# WirelessTransceiver_RevB.net
KiCad netlist of a schematic drawn in EAGLE
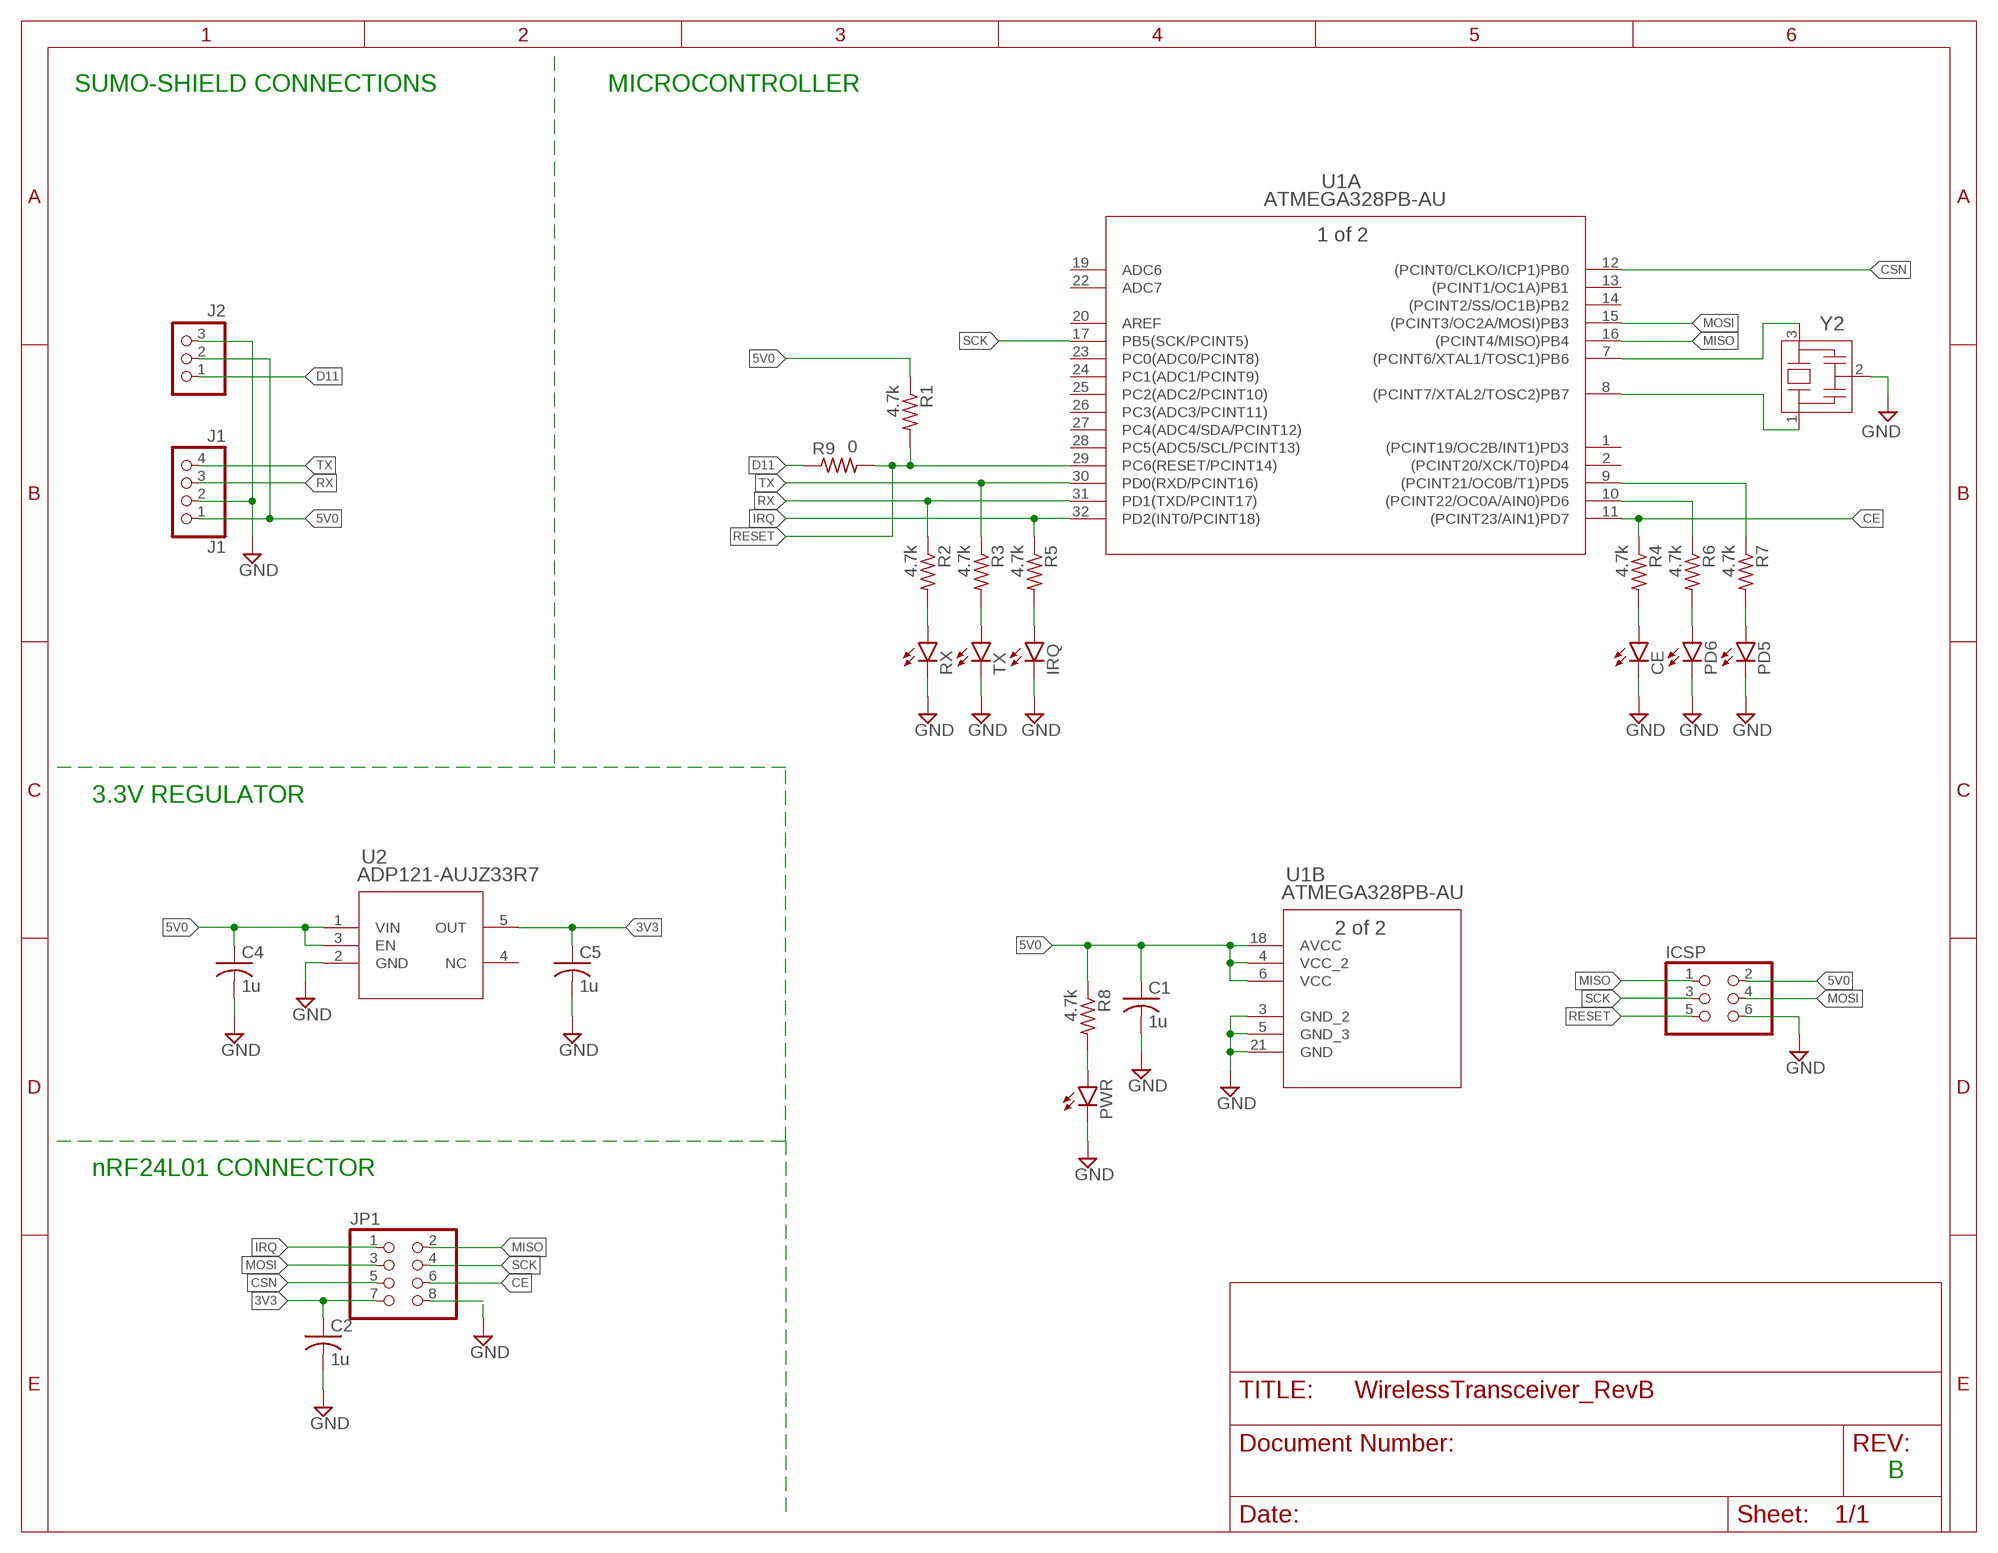
[diagram p0: schematic, sheet 1]

(export (version "E")
  (design (tool "Eeschema 10.0.6"))
  (components
    (comp (ref "C1")
      (value "1u")
      (footprint "eagle-import:C0805")
      (libsource (lib "eagle-import") (part "C-USC0805"))
    )
    (comp (ref "C2")
      (value "1u")
      (footprint "eagle-import:C0805")
      (libsource (lib "eagle-import") (part "C-USC0805"))
    )
    (comp (ref "C4")
      (value "1u")
      (footprint "eagle-import:C0805")
      (libsource (lib "eagle-import") (part "C-USC0805"))
    )
    (comp (ref "C5")
      (value "1u")
      (footprint "eagle-import:C0805")
      (libsource (lib "eagle-import") (part "C-USC0805"))
    )
    (comp (ref "CE")
      (value "LEDSML0805")
      (footprint "eagle-import:SML0805")
      (libsource (lib "eagle-import") (part "LEDSML0805"))
    )
    (comp (ref "ICSP")
      (value "PINHD-2X3")
      (footprint "eagle-import:2X03")
      (libsource (lib "eagle-import") (part "PINHD-2X3"))
    )
    (comp (ref "IRQ")
      (value "LEDSML0805")
      (footprint "eagle-import:SML0805")
      (libsource (lib "eagle-import") (part "LEDSML0805"))
    )
    (comp (ref "J1")
      (value "J1")
      (footprint "eagle-import:1X04")
      (libsource (lib "eagle-import") (part "PINHD-1X4"))
    )
    (comp (ref "J2")
      (value "PINHD-1X3")
      (footprint "eagle-import:1X03")
      (libsource (lib "eagle-import") (part "PINHD-1X3"))
    )
    (comp (ref "JP1")
      (value "PINHD-2X4")
      (footprint "eagle-import:2X04")
      (libsource (lib "eagle-import") (part "PINHD-2X4"))
    )
    (comp (ref "PD5")
      (value "LEDSML0805")
      (footprint "eagle-import:SML0805")
      (libsource (lib "eagle-import") (part "LEDSML0805"))
    )
    (comp (ref "PD6")
      (value "LEDSML0805")
      (footprint "eagle-import:SML0805")
      (libsource (lib "eagle-import") (part "LEDSML0805"))
    )
    (comp (ref "PWR")
      (value "LEDSML0805")
      (footprint "eagle-import:SML0805")
      (libsource (lib "eagle-import") (part "LEDSML0805"))
    )
    (comp (ref "R1")
      (value "4.7k")
      (footprint "eagle-import:R0805")
      (libsource (lib "eagle-import") (part "R-US_R0805"))
    )
    (comp (ref "R2")
      (value "4.7k")
      (footprint "eagle-import:R0805")
      (libsource (lib "eagle-import") (part "R-US_R0805"))
    )
    (comp (ref "R3")
      (value "4.7k")
      (footprint "eagle-import:R0805")
      (libsource (lib "eagle-import") (part "R-US_R0805"))
    )
    (comp (ref "R4")
      (value "4.7k")
      (footprint "eagle-import:R0805")
      (libsource (lib "eagle-import") (part "R-US_R0805"))
    )
    (comp (ref "R5")
      (value "4.7k")
      (footprint "eagle-import:R0805")
      (libsource (lib "eagle-import") (part "R-US_R0805"))
    )
    (comp (ref "R6")
      (value "4.7k")
      (footprint "eagle-import:R0805")
      (libsource (lib "eagle-import") (part "R-US_R0805"))
    )
    (comp (ref "R7")
      (value "4.7k")
      (footprint "eagle-import:R0805")
      (libsource (lib "eagle-import") (part "R-US_R0805"))
    )
    (comp (ref "R8")
      (value "4.7k")
      (footprint "eagle-import:R0805")
      (libsource (lib "eagle-import") (part "R-US_R0805"))
    )
    (comp (ref "R9")
      (value "0")
      (footprint "eagle-import:R0805")
      (libsource (lib "eagle-import") (part "R-US_R0805"))
    )
    (comp (ref "RX")
      (value "LEDSML0805")
      (footprint "eagle-import:SML0805")
      (libsource (lib "eagle-import") (part "LEDSML0805"))
    )
    (comp (ref "TX")
      (value "LEDSML0805")
      (footprint "eagle-import:SML0805")
      (libsource (lib "eagle-import") (part "LEDSML0805"))
    )
    (comp (ref "U1")
      (value "ATMEGA328PB-AU")
      (footprint "eagle-import:32A_MCH")
      (fields (field (name "COPYRIGHT") "Copyright (C) 2023 Ultra Librarian. All rights reserved."))
      (libsource (lib "eagle-import") (part "ATMEGA328PB-AU"))
    )
    (comp (ref "U2")
      (value "ADP121-AUJZ33R7")
      (footprint "eagle-import:UJ_5_ADI")
      (fields (field (name "COPYRIGHT") "Copyright (C) 2023 Ultra Librarian. All rights reserved."))
      (libsource (lib "eagle-import") (part "ADP121-AUJZ33R7"))
    )
    (comp (ref "Y2")
      (value "CSTNE16M0V530000R0")
      (footprint "eagle-import:CSTNE16M0V530000R0_MUR")
      (fields (field (name "COPYRIGHT") "Copyright (C) 2023 Ultra Librarian. All rights reserved."))
      (libsource (lib "eagle-import") (part "CSTNE16M0V530000R0"))
    )
  )
  (nets
    (net (code "1") (name "3V3") (class "Default")
      (node (ref "C2") (pin "1") (pinfunction "1_1") (pintype "passive"))
      (node (ref "C5") (pin "1") (pinfunction "1_1") (pintype "passive"))
      (node (ref "JP1") (pin "7") (pinfunction "7_7") (pintype "passive"))
      (node (ref "U2") (pin "5") (pinfunction "OUT_5") (pintype "output"))
    )
    (net (code "2") (name "5V0") (class "Default")
      (node (ref "C1") (pin "1") (pinfunction "1_1") (pintype "passive"))
      (node (ref "C4") (pin "1") (pinfunction "1_1") (pintype "passive"))
      (node (ref "ICSP") (pin "2") (pinfunction "2_2") (pintype "passive"))
      (node (ref "J1") (pin "1") (pinfunction "1_1") (pintype "passive"))
      (node (ref "J2") (pin "2") (pinfunction "2_2") (pintype "passive"))
      (node (ref "R1") (pin "1") (pinfunction "1_1") (pintype "passive"))
      (node (ref "R8") (pin "1") (pinfunction "1_1") (pintype "passive"))
      (node (ref "U1") (pin "18") (pinfunction "AVCC_18") (pintype "power_in"))
      (node (ref "U1") (pin "4") (pinfunction "VCC_2_4") (pintype "power_in"))
      (node (ref "U1") (pin "6") (pinfunction "VCC_6") (pintype "power_in"))
      (node (ref "U2") (pin "1") (pinfunction "VIN_1") (pintype "input"))
      (node (ref "U2") (pin "3") (pinfunction "EN_3") (pintype "input"))
    )
    (net (code "3") (name "CE") (class "Default")
      (node (ref "JP1") (pin "6") (pinfunction "6_6") (pintype "passive"))
      (node (ref "R4") (pin "1") (pinfunction "1_1") (pintype "passive"))
      (node (ref "U1") (pin "11") (pinfunction "(PCINT23/AIN1)PD7_11") (pintype "bidirectional"))
    )
    (net (code "4") (name "CSN") (class "Default")
      (node (ref "JP1") (pin "5") (pinfunction "5_5") (pintype "passive"))
      (node (ref "U1") (pin "12") (pinfunction "(PCINT0/CLKO/ICP1)PB0_12") (pintype "bidirectional"))
    )
    (net (code "5") (name "D11") (class "Default")
      (node (ref "J2") (pin "1") (pinfunction "1_1") (pintype "passive"))
      (node (ref "R9") (pin "1") (pinfunction "1_1") (pintype "passive"))
    )
    (net (code "6") (name "GND") (class "Default")
      (node (ref "C1") (pin "2") (pinfunction "2_2") (pintype "passive"))
      (node (ref "C2") (pin "2") (pinfunction "2_2") (pintype "passive"))
      (node (ref "C4") (pin "2") (pinfunction "2_2") (pintype "passive"))
      (node (ref "C5") (pin "2") (pinfunction "2_2") (pintype "passive"))
      (node (ref "CE") (pin "C") (pinfunction "C_C") (pintype "passive"))
      (node (ref "ICSP") (pin "6") (pinfunction "6_6") (pintype "passive"))
      (node (ref "IRQ") (pin "C") (pinfunction "C_C") (pintype "passive"))
      (node (ref "J1") (pin "2") (pinfunction "2_2") (pintype "passive"))
      (node (ref "J2") (pin "3") (pinfunction "3_3") (pintype "passive"))
      (node (ref "JP1") (pin "8") (pinfunction "8_8") (pintype "passive"))
      (node (ref "PD5") (pin "C") (pinfunction "C_C") (pintype "passive"))
      (node (ref "PD6") (pin "C") (pinfunction "C_C") (pintype "passive"))
      (node (ref "PWR") (pin "C") (pinfunction "C_C") (pintype "passive"))
      (node (ref "RX") (pin "C") (pinfunction "C_C") (pintype "passive"))
      (node (ref "TX") (pin "C") (pinfunction "C_C") (pintype "passive"))
      (node (ref "U1") (pin "21") (pinfunction "GND_21") (pintype "power_in"))
      (node (ref "U1") (pin "3") (pinfunction "GND_2_3") (pintype "power_in"))
      (node (ref "U1") (pin "5") (pinfunction "GND_3_5") (pintype "power_in"))
      (node (ref "U2") (pin "2") (pinfunction "GND_2") (pintype "power_in"))
      (node (ref "Y2") (pin "2") (pinfunction "2_2") (pintype "passive"))
    )
    (net (code "7") (name "IRQ") (class "Default")
      (node (ref "JP1") (pin "1") (pinfunction "1_1") (pintype "passive"))
      (node (ref "R5") (pin "1") (pinfunction "1_1") (pintype "passive"))
      (node (ref "U1") (pin "32") (pinfunction "PD2(INT0/PCINT18)_32") (pintype "bidirectional"))
    )
    (net (code "8") (name "MISO") (class "Default")
      (node (ref "ICSP") (pin "1") (pinfunction "1_1") (pintype "passive"))
      (node (ref "JP1") (pin "2") (pinfunction "2_2") (pintype "passive"))
      (node (ref "U1") (pin "16") (pinfunction "(PCINT4/MISO)PB4_16") (pintype "bidirectional"))
    )
    (net (code "9") (name "MOSI") (class "Default")
      (node (ref "ICSP") (pin "4") (pinfunction "4_4") (pintype "passive"))
      (node (ref "JP1") (pin "3") (pinfunction "3_3") (pintype "passive"))
      (node (ref "U1") (pin "15") (pinfunction "(PCINT3/OC2A/MOSI)PB3_15") (pintype "bidirectional"))
    )
    (net (code "10") (name "Net-(CE-PadA)") (class "Default")
      (node (ref "CE") (pin "A") (pinfunction "A_A") (pintype "passive"))
      (node (ref "R4") (pin "2") (pinfunction "2_2") (pintype "passive"))
    )
    (net (code "11") (name "Net-(IRQ-PadA)") (class "Default")
      (node (ref "IRQ") (pin "A") (pinfunction "A_A") (pintype "passive"))
      (node (ref "R5") (pin "2") (pinfunction "2_2") (pintype "passive"))
    )
    (net (code "12") (name "Net-(PD5-PadA)") (class "Default")
      (node (ref "PD5") (pin "A") (pinfunction "A_A") (pintype "passive"))
      (node (ref "R7") (pin "2") (pinfunction "2_2") (pintype "passive"))
    )
    (net (code "13") (name "Net-(PD6-PadA)") (class "Default")
      (node (ref "PD6") (pin "A") (pinfunction "A_A") (pintype "passive"))
      (node (ref "R6") (pin "2") (pinfunction "2_2") (pintype "passive"))
    )
    (net (code "14") (name "Net-(PWR-PadA)") (class "Default")
      (node (ref "PWR") (pin "A") (pinfunction "A_A") (pintype "passive"))
      (node (ref "R8") (pin "2") (pinfunction "2_2") (pintype "passive"))
    )
    (net (code "15") (name "Net-(R2-Pad2)") (class "Default")
      (node (ref "R2") (pin "2") (pinfunction "2_2") (pintype "passive"))
      (node (ref "RX") (pin "A") (pinfunction "A_A") (pintype "passive"))
    )
    (net (code "16") (name "Net-(R3-Pad2)") (class "Default")
      (node (ref "R3") (pin "2") (pinfunction "2_2") (pintype "passive"))
      (node (ref "TX") (pin "A") (pinfunction "A_A") (pintype "passive"))
    )
    (net (code "17") (name "Net-(U1A-(PCINT6{slash}XTAL1{slash}TOSC1)PB6)") (class "Default")
      (node (ref "U1") (pin "7") (pinfunction "(PCINT6/XTAL1/TOSC1)PB6_7") (pintype "bidirectional"))
      (node (ref "Y2") (pin "3") (pinfunction "3_3") (pintype "output"))
    )
    (net (code "18") (name "Net-(U1A-(PCINT7{slash}XTAL2{slash}TOSC2)PB7)") (class "Default")
      (node (ref "U1") (pin "8") (pinfunction "(PCINT7/XTAL2/TOSC2)PB7_8") (pintype "bidirectional"))
      (node (ref "Y2") (pin "1") (pinfunction "1_1") (pintype "input"))
    )
    (net (code "19") (name "Net-(U1A-(PCINT21{slash}OC0B{slash}T1)PD5)") (class "Default")
      (node (ref "R7") (pin "1") (pinfunction "1_1") (pintype "passive"))
      (node (ref "U1") (pin "9") (pinfunction "(PCINT21/OC0B/T1)PD5_9") (pintype "bidirectional"))
    )
    (net (code "20") (name "Net-(U1A-(PCINT22{slash}OC0A{slash}AIN0)PD6)") (class "Default")
      (node (ref "R6") (pin "1") (pinfunction "1_1") (pintype "passive"))
      (node (ref "U1") (pin "10") (pinfunction "(PCINT22/OC0A/AIN0)PD6_10") (pintype "bidirectional"))
    )
    (net (code "21") (name "RESET") (class "Default")
      (node (ref "ICSP") (pin "5") (pinfunction "5_5") (pintype "passive"))
      (node (ref "R1") (pin "2") (pinfunction "2_2") (pintype "passive"))
      (node (ref "R9") (pin "2") (pinfunction "2_2") (pintype "passive"))
      (node (ref "U1") (pin "29") (pinfunction "PC6(RESET/PCINT14)_29") (pintype "bidirectional"))
    )
    (net (code "22") (name "RX") (class "Default")
      (node (ref "J1") (pin "3") (pinfunction "3_3") (pintype "passive"))
      (node (ref "R2") (pin "1") (pinfunction "1_1") (pintype "passive"))
      (node (ref "U1") (pin "31") (pinfunction "PD1(TXD/PCINT17)_31") (pintype "bidirectional"))
    )
    (net (code "23") (name "SCK") (class "Default")
      (node (ref "ICSP") (pin "3") (pinfunction "3_3") (pintype "passive"))
      (node (ref "JP1") (pin "4") (pinfunction "4_4") (pintype "passive"))
      (node (ref "U1") (pin "17") (pinfunction "PB5(SCK/PCINT5)_17") (pintype "bidirectional"))
    )
    (net (code "24") (name "TX") (class "Default")
      (node (ref "J1") (pin "4") (pinfunction "4_4") (pintype "passive"))
      (node (ref "R3") (pin "1") (pinfunction "1_1") (pintype "passive"))
      (node (ref "U1") (pin "30") (pinfunction "PD0(RXD/PCINT16)_30") (pintype "bidirectional"))
    )
    (net (code "25") (name "unconnected-(U1A-(PCINT1{slash}OC1A)PB1-Pad13)") (class "Default")
      (node (ref "U1") (pin "13") (pinfunction "(PCINT1/OC1A)PB1_13") (pintype "bidirectional"))
    )
    (net (code "26") (name "unconnected-(U1A-(PCINT2{slash}SS{slash}OC1B)PB2-Pad14)") (class "Default")
      (node (ref "U1") (pin "14") (pinfunction "(PCINT2/SS/OC1B)PB2_14") (pintype "bidirectional"))
    )
    (net (code "27") (name "unconnected-(U1A-(PCINT19{slash}OC2B{slash}INT1)PD3-Pad1)") (class "Default")
      (node (ref "U1") (pin "1") (pinfunction "(PCINT19/OC2B/INT1)PD3_1") (pintype "bidirectional"))
    )
    (net (code "28") (name "unconnected-(U1A-(PCINT20{slash}XCK{slash}T0)PD4-Pad2)") (class "Default")
      (node (ref "U1") (pin "2") (pinfunction "(PCINT20/XCK/T0)PD4_2") (pintype "bidirectional"))
    )
    (net (code "29") (name "unconnected-(U1A-ADC6-Pad19)") (class "Default")
      (node (ref "U1") (pin "19") (pinfunction "ADC6_19") (pintype "input"))
    )
    (net (code "30") (name "unconnected-(U1A-ADC7-Pad22)") (class "Default")
      (node (ref "U1") (pin "22") (pinfunction "ADC7_22") (pintype "input"))
    )
    (net (code "31") (name "unconnected-(U1A-AREF-Pad20)") (class "Default")
      (node (ref "U1") (pin "20") (pinfunction "AREF_20") (pintype "passive"))
    )
    (net (code "32") (name "unconnected-(U1A-PC0(ADC0{slash}PCINT8)-Pad23)") (class "Default")
      (node (ref "U1") (pin "23") (pinfunction "PC0(ADC0/PCINT8)_23") (pintype "bidirectional"))
    )
    (net (code "33") (name "unconnected-(U1A-PC1(ADC1{slash}PCINT9)-Pad24)") (class "Default")
      (node (ref "U1") (pin "24") (pinfunction "PC1(ADC1/PCINT9)_24") (pintype "bidirectional"))
    )
    (net (code "34") (name "unconnected-(U1A-PC2(ADC2{slash}PCINT10)-Pad25)") (class "Default")
      (node (ref "U1") (pin "25") (pinfunction "PC2(ADC2/PCINT10)_25") (pintype "bidirectional"))
    )
    (net (code "35") (name "unconnected-(U1A-PC3(ADC3{slash}PCINT11)-Pad26)") (class "Default")
      (node (ref "U1") (pin "26") (pinfunction "PC3(ADC3/PCINT11)_26") (pintype "bidirectional"))
    )
    (net (code "36") (name "unconnected-(U1A-PC4(ADC4{slash}SDA{slash}PCINT12)-Pad27)") (class "Default")
      (node (ref "U1") (pin "27") (pinfunction "PC4(ADC4/SDA/PCINT12)_27") (pintype "bidirectional"))
    )
    (net (code "37") (name "unconnected-(U1A-PC5(ADC5{slash}SCL{slash}PCINT13)-Pad28)") (class "Default")
      (node (ref "U1") (pin "28") (pinfunction "PC5(ADC5/SCL/PCINT13)_28") (pintype "bidirectional"))
    )
    (net (code "38") (name "unconnected-(U2-NC-Pad4)") (class "Default")
      (node (ref "U2") (pin "4") (pinfunction "NC_4") (pintype "no_connect"))
    )
  )
)
